# ShiftregisterTeil1.net
KiCad netlist of a schematic drawn in Altium Designer
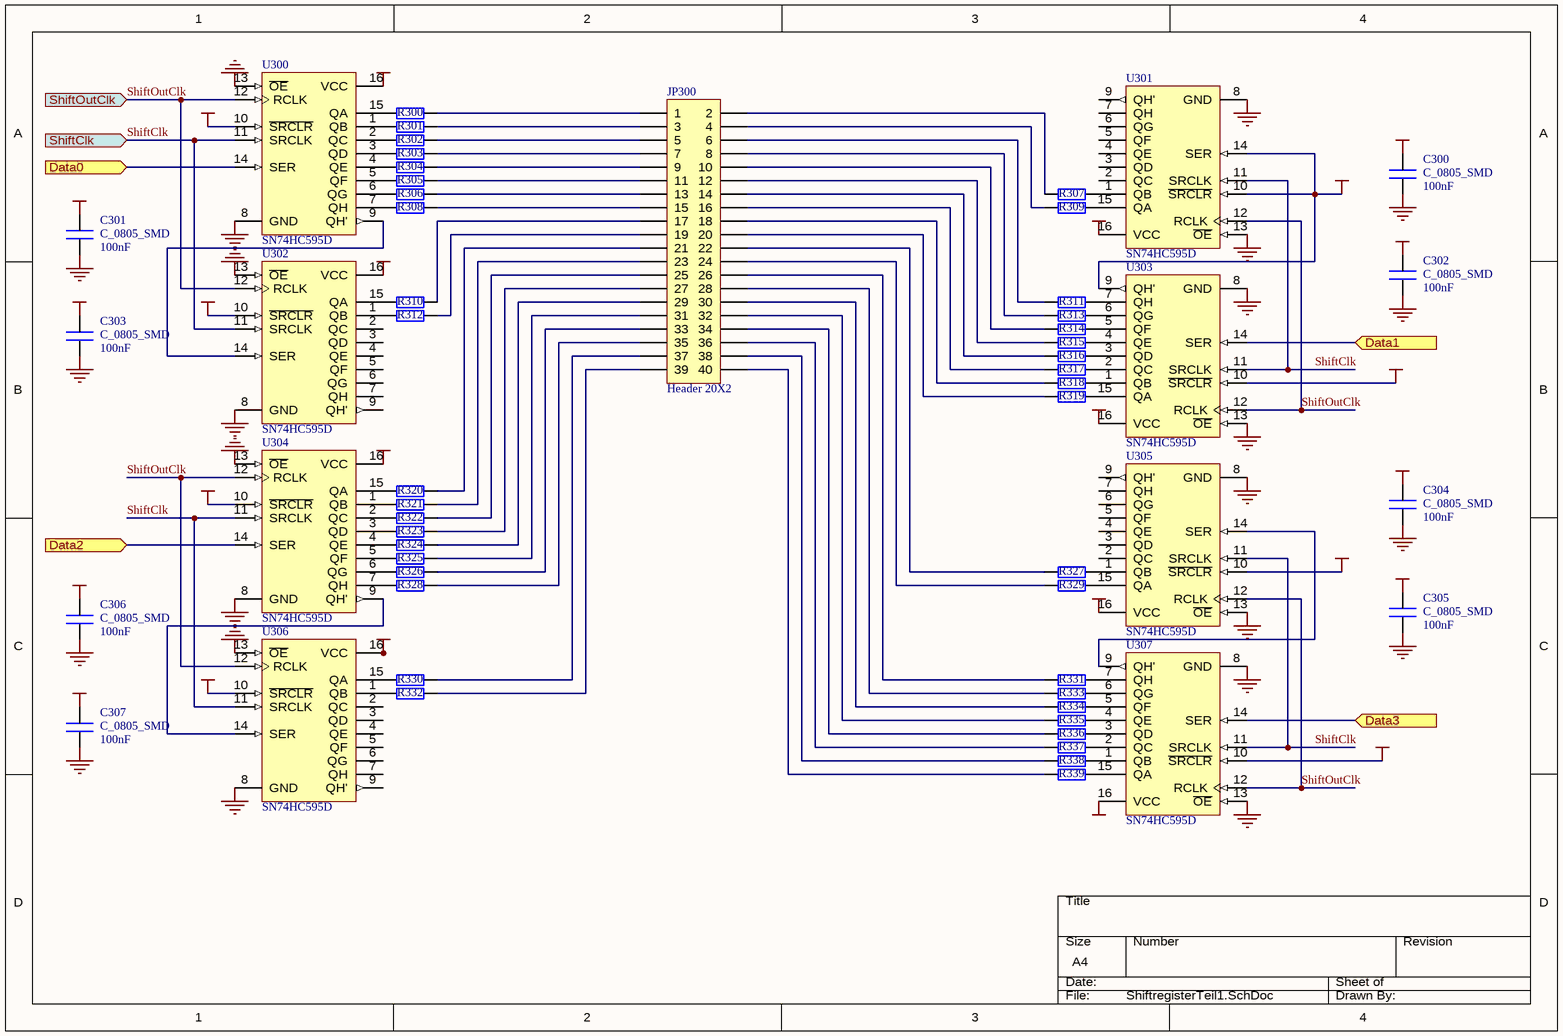
[diagram p0: ShiftregisterTeil1.SchDoc]

(export (version "E")
  (design (tool "Eeschema 10.0.6"))
  (components
    (comp (ref "C300")
      (value "C_0805_SMD")
      (footprint "0805_R")
      (description "Kondensator in SMD-Bauform")
      (fields (field (name "ALTIUM_UNNAMED_1") "100nF"))
      (libsource (lib "Kondensatoren") (part "C_0805_SMD"))
    )
    (comp (ref "C301")
      (value "C_0805_SMD")
      (footprint "0805_R")
      (description "Kondensator in SMD-Bauform")
      (fields (field (name "ALTIUM_UNNAMED_1") "100nF"))
      (libsource (lib "Kondensatoren") (part "C_0805_SMD"))
    )
    (comp (ref "C302")
      (value "C_0805_SMD")
      (footprint "0805_R")
      (description "Kondensator in SMD-Bauform")
      (fields (field (name "ALTIUM_UNNAMED_1") "100nF"))
      (libsource (lib "Kondensatoren") (part "C_0805_SMD"))
    )
    (comp (ref "C303")
      (value "C_0805_SMD")
      (footprint "0805_R")
      (description "Kondensator in SMD-Bauform")
      (fields (field (name "ALTIUM_UNNAMED_1") "100nF"))
      (libsource (lib "Kondensatoren") (part "C_0805_SMD"))
    )
    (comp (ref "C304")
      (value "C_0805_SMD")
      (footprint "0805_R")
      (description "Kondensator in SMD-Bauform")
      (fields (field (name "ALTIUM_UNNAMED_1") "100nF"))
      (libsource (lib "Kondensatoren") (part "C_0805_SMD"))
    )
    (comp (ref "C305")
      (value "C_0805_SMD")
      (footprint "0805_R")
      (description "Kondensator in SMD-Bauform")
      (fields (field (name "ALTIUM_UNNAMED_1") "100nF"))
      (libsource (lib "Kondensatoren") (part "C_0805_SMD"))
    )
    (comp (ref "C306")
      (value "C_0805_SMD")
      (footprint "0805_R")
      (description "Kondensator in SMD-Bauform")
      (fields (field (name "ALTIUM_UNNAMED_1") "100nF"))
      (libsource (lib "Kondensatoren") (part "C_0805_SMD"))
    )
    (comp (ref "C307")
      (value "C_0805_SMD")
      (footprint "0805_R")
      (description "Kondensator in SMD-Bauform")
      (fields (field (name "ALTIUM_UNNAMED_1") "100nF"))
      (libsource (lib "Kondensatoren") (part "C_0805_SMD"))
    )
    (comp (ref "JP300")
      (value "Header 20X2")
      (footprint "HDR2X20")
      (description "Header, 20-Pin, Dual row")
      (fields (field (name "PUBLISHER") "Altium Limited"))
      (libsource (lib "Miscellaneous Connectors") (part "Header 20X2"))
    )
    (comp (ref "R300")
      (value "PullUp")
      (footprint "CR2012-0805")
      (description "Resistor")
      (fields (field (name "PUBLISHER") "Altium Limited"))
      (libsource (lib "Miscellaneous Devices") (part "Res2"))
    )
    (comp (ref "R301")
      (value "PullUp")
      (footprint "CR2012-0805")
      (description "Resistor")
      (fields (field (name "PUBLISHER") "Altium Limited"))
      (libsource (lib "Miscellaneous Devices") (part "Res2"))
    )
    (comp (ref "R302")
      (value "PullUp")
      (footprint "CR2012-0805")
      (description "Resistor")
      (fields (field (name "PUBLISHER") "Altium Limited"))
      (libsource (lib "Miscellaneous Devices") (part "Res2"))
    )
    (comp (ref "R303")
      (value "PullUp")
      (footprint "CR2012-0805")
      (description "Resistor")
      (fields (field (name "PUBLISHER") "Altium Limited"))
      (libsource (lib "Miscellaneous Devices") (part "Res2"))
    )
    (comp (ref "R304")
      (value "PullUp")
      (footprint "CR2012-0805")
      (description "Resistor")
      (fields (field (name "PUBLISHER") "Altium Limited"))
      (libsource (lib "Miscellaneous Devices") (part "Res2"))
    )
    (comp (ref "R305")
      (value "PullUp")
      (footprint "CR2012-0805")
      (description "Resistor")
      (fields (field (name "PUBLISHER") "Altium Limited"))
      (libsource (lib "Miscellaneous Devices") (part "Res2"))
    )
    (comp (ref "R306")
      (value "PullUp")
      (footprint "CR2012-0805")
      (description "Resistor")
      (fields (field (name "PUBLISHER") "Altium Limited"))
      (libsource (lib "Miscellaneous Devices") (part "Res2"))
    )
    (comp (ref "R307")
      (value "PullUp")
      (footprint "CR2012-0805")
      (description "Resistor")
      (fields (field (name "PUBLISHER") "Altium Limited"))
      (libsource (lib "Miscellaneous Devices") (part "Res2"))
    )
    (comp (ref "R308")
      (value "PullUp")
      (footprint "CR2012-0805")
      (description "Resistor")
      (fields (field (name "PUBLISHER") "Altium Limited"))
      (libsource (lib "Miscellaneous Devices") (part "Res2"))
    )
    (comp (ref "R309")
      (value "PullUp")
      (footprint "CR2012-0805")
      (description "Resistor")
      (fields (field (name "PUBLISHER") "Altium Limited"))
      (libsource (lib "Miscellaneous Devices") (part "Res2"))
    )
    (comp (ref "R310")
      (value "PullUp")
      (footprint "CR2012-0805")
      (description "Resistor")
      (fields (field (name "PUBLISHER") "Altium Limited"))
      (libsource (lib "Miscellaneous Devices") (part "Res2"))
    )
    (comp (ref "R311")
      (value "PullUp")
      (footprint "CR2012-0805")
      (description "Resistor")
      (fields (field (name "PUBLISHER") "Altium Limited"))
      (libsource (lib "Miscellaneous Devices") (part "Res2"))
    )
    (comp (ref "R312")
      (value "PullUp")
      (footprint "CR2012-0805")
      (description "Resistor")
      (fields (field (name "PUBLISHER") "Altium Limited"))
      (libsource (lib "Miscellaneous Devices") (part "Res2"))
    )
    (comp (ref "R313")
      (value "PullUp")
      (footprint "CR2012-0805")
      (description "Resistor")
      (fields (field (name "PUBLISHER") "Altium Limited"))
      (libsource (lib "Miscellaneous Devices") (part "Res2"))
    )
    (comp (ref "R314")
      (value "PullUp")
      (footprint "CR2012-0805")
      (description "Resistor")
      (fields (field (name "PUBLISHER") "Altium Limited"))
      (libsource (lib "Miscellaneous Devices") (part "Res2"))
    )
    (comp (ref "R315")
      (value "PullUp")
      (footprint "CR2012-0805")
      (description "Resistor")
      (fields (field (name "PUBLISHER") "Altium Limited"))
      (libsource (lib "Miscellaneous Devices") (part "Res2"))
    )
    (comp (ref "R316")
      (value "PullUp")
      (footprint "CR2012-0805")
      (description "Resistor")
      (fields (field (name "PUBLISHER") "Altium Limited"))
      (libsource (lib "Miscellaneous Devices") (part "Res2"))
    )
    (comp (ref "R317")
      (value "PullUp")
      (footprint "CR2012-0805")
      (description "Resistor")
      (fields (field (name "PUBLISHER") "Altium Limited"))
      (libsource (lib "Miscellaneous Devices") (part "Res2"))
    )
    (comp (ref "R318")
      (value "PullUp")
      (footprint "CR2012-0805")
      (description "Resistor")
      (fields (field (name "PUBLISHER") "Altium Limited"))
      (libsource (lib "Miscellaneous Devices") (part "Res2"))
    )
    (comp (ref "R319")
      (value "PullUp")
      (footprint "CR2012-0805")
      (description "Resistor")
      (fields (field (name "PUBLISHER") "Altium Limited"))
      (libsource (lib "Miscellaneous Devices") (part "Res2"))
    )
    (comp (ref "R320")
      (value "PullUp")
      (footprint "CR2012-0805")
      (description "Resistor")
      (fields (field (name "PUBLISHER") "Altium Limited"))
      (libsource (lib "Miscellaneous Devices") (part "Res2"))
    )
    (comp (ref "R321")
      (value "PullUp")
      (footprint "CR2012-0805")
      (description "Resistor")
      (fields (field (name "PUBLISHER") "Altium Limited"))
      (libsource (lib "Miscellaneous Devices") (part "Res2"))
    )
    (comp (ref "R322")
      (value "PullUp")
      (footprint "CR2012-0805")
      (description "Resistor")
      (fields (field (name "PUBLISHER") "Altium Limited"))
      (libsource (lib "Miscellaneous Devices") (part "Res2"))
    )
    (comp (ref "R323")
      (value "PullUp")
      (footprint "CR2012-0805")
      (description "Resistor")
      (fields (field (name "PUBLISHER") "Altium Limited"))
      (libsource (lib "Miscellaneous Devices") (part "Res2"))
    )
    (comp (ref "R324")
      (value "PullUp")
      (footprint "CR2012-0805")
      (description "Resistor")
      (fields (field (name "PUBLISHER") "Altium Limited"))
      (libsource (lib "Miscellaneous Devices") (part "Res2"))
    )
    (comp (ref "R325")
      (value "PullUp")
      (footprint "CR2012-0805")
      (description "Resistor")
      (fields (field (name "PUBLISHER") "Altium Limited"))
      (libsource (lib "Miscellaneous Devices") (part "Res2"))
    )
    (comp (ref "R326")
      (value "PullUp")
      (footprint "CR2012-0805")
      (description "Resistor")
      (fields (field (name "PUBLISHER") "Altium Limited"))
      (libsource (lib "Miscellaneous Devices") (part "Res2"))
    )
    (comp (ref "R327")
      (value "PullUp")
      (footprint "CR2012-0805")
      (description "Resistor")
      (fields (field (name "PUBLISHER") "Altium Limited"))
      (libsource (lib "Miscellaneous Devices") (part "Res2"))
    )
    (comp (ref "R328")
      (value "PullUp")
      (footprint "CR2012-0805")
      (description "Resistor")
      (fields (field (name "PUBLISHER") "Altium Limited"))
      (libsource (lib "Miscellaneous Devices") (part "Res2"))
    )
    (comp (ref "R329")
      (value "PullUp")
      (footprint "CR2012-0805")
      (description "Resistor")
      (fields (field (name "PUBLISHER") "Altium Limited"))
      (libsource (lib "Miscellaneous Devices") (part "Res2"))
    )
    (comp (ref "R330")
      (value "PullUp")
      (footprint "CR2012-0805")
      (description "Resistor")
      (fields (field (name "PUBLISHER") "Altium Limited"))
      (libsource (lib "Miscellaneous Devices") (part "Res2"))
    )
    (comp (ref "R331")
      (value "PullUp")
      (footprint "CR2012-0805")
      (description "Resistor")
      (fields (field (name "PUBLISHER") "Altium Limited"))
      (libsource (lib "Miscellaneous Devices") (part "Res2"))
    )
    (comp (ref "R332")
      (value "PullUp")
      (footprint "CR2012-0805")
      (description "Resistor")
      (fields (field (name "PUBLISHER") "Altium Limited"))
      (libsource (lib "Miscellaneous Devices") (part "Res2"))
    )
    (comp (ref "R333")
      (value "PullUp")
      (footprint "CR2012-0805")
      (description "Resistor")
      (fields (field (name "PUBLISHER") "Altium Limited"))
      (libsource (lib "Miscellaneous Devices") (part "Res2"))
    )
    (comp (ref "R334")
      (value "PullUp")
      (footprint "CR2012-0805")
      (description "Resistor")
      (fields (field (name "PUBLISHER") "Altium Limited"))
      (libsource (lib "Miscellaneous Devices") (part "Res2"))
    )
    (comp (ref "R335")
      (value "PullUp")
      (footprint "CR2012-0805")
      (description "Resistor")
      (fields (field (name "PUBLISHER") "Altium Limited"))
      (libsource (lib "Miscellaneous Devices") (part "Res2"))
    )
    (comp (ref "R336")
      (value "PullUp")
      (footprint "CR2012-0805")
      (description "Resistor")
      (fields (field (name "PUBLISHER") "Altium Limited"))
      (libsource (lib "Miscellaneous Devices") (part "Res2"))
    )
    (comp (ref "R337")
      (value "PullUp")
      (footprint "CR2012-0805")
      (description "Resistor")
      (fields (field (name "PUBLISHER") "Altium Limited"))
      (libsource (lib "Miscellaneous Devices") (part "Res2"))
    )
    (comp (ref "R338")
      (value "PullUp")
      (footprint "CR2012-0805")
      (description "Resistor")
      (fields (field (name "PUBLISHER") "Altium Limited"))
      (libsource (lib "Miscellaneous Devices") (part "Res2"))
    )
    (comp (ref "R339")
      (value "PullUp")
      (footprint "CR2012-0805")
      (description "Resistor")
      (fields (field (name "PUBLISHER") "Altium Limited"))
      (libsource (lib "Miscellaneous Devices") (part "Res2"))
    )
    (comp (ref "U300")
      (value "SN74HC595D")
      (footprint "D016")
      (description "8-Bit Shift Register with 3-State Output Registers")
      (fields (field (name "PUBLISHER") "Altium Limited"))
      (libsource (lib "TI Logic Register") (part "SN74HC595D"))
    )
    (comp (ref "U301")
      (value "SN74HC595D")
      (footprint "D016")
      (description "8-Bit Shift Register with 3-State Output Registers")
      (fields (field (name "PUBLISHER") "Altium Limited"))
      (libsource (lib "") (part "SN74HC595D_1"))
    )
    (comp (ref "U302")
      (value "SN74HC595D")
      (footprint "D016")
      (description "8-Bit Shift Register with 3-State Output Registers")
      (fields (field (name "PUBLISHER") "Altium Limited"))
      (libsource (lib "TI Logic Register") (part "SN74HC595D"))
    )
    (comp (ref "U303")
      (value "SN74HC595D")
      (footprint "D016")
      (description "8-Bit Shift Register with 3-State Output Registers")
      (fields (field (name "PUBLISHER") "Altium Limited"))
      (libsource (lib "") (part "SN74HC595D_1"))
    )
    (comp (ref "U304")
      (value "SN74HC595D")
      (footprint "D016")
      (description "8-Bit Shift Register with 3-State Output Registers")
      (fields (field (name "PUBLISHER") "Altium Limited"))
      (libsource (lib "TI Logic Register") (part "SN74HC595D"))
    )
    (comp (ref "U305")
      (value "SN74HC595D")
      (footprint "D016")
      (description "8-Bit Shift Register with 3-State Output Registers")
      (fields (field (name "PUBLISHER") "Altium Limited"))
      (libsource (lib "") (part "SN74HC595D_1"))
    )
    (comp (ref "U306")
      (value "SN74HC595D")
      (footprint "D016")
      (description "8-Bit Shift Register with 3-State Output Registers")
      (fields (field (name "PUBLISHER") "Altium Limited"))
      (libsource (lib "TI Logic Register") (part "SN74HC595D"))
    )
    (comp (ref "U307")
      (value "SN74HC595D")
      (footprint "D016")
      (description "8-Bit Shift Register with 3-State Output Registers")
      (fields (field (name "PUBLISHER") "Altium Limited"))
      (libsource (lib "") (part "SN74HC595D_1"))
    )
  )
  (nets
    (net (code "1") (name "/Data0") (class "Default")
      (node (ref "U300") (pin "14") (pinfunction "SER_14") (pintype "input"))
    )
    (net (code "2") (name "/Data1") (class "Default")
      (node (ref "U303") (pin "14") (pinfunction "SER_14") (pintype "input"))
    )
    (net (code "3") (name "/Data2") (class "Default")
      (node (ref "U304") (pin "14") (pinfunction "SER_14") (pintype "input"))
    )
    (net (code "4") (name "/Data3") (class "Default")
      (node (ref "U307") (pin "14") (pinfunction "SER_14") (pintype "input"))
    )
    (net (code "5") (name "/ShiftClk") (class "Default")
      (node (ref "U300") (pin "11") (pinfunction "SRCLK_11") (pintype "input"))
      (node (ref "U301") (pin "11") (pinfunction "SRCLK_11") (pintype "input"))
      (node (ref "U302") (pin "11") (pinfunction "SRCLK_11") (pintype "input"))
      (node (ref "U303") (pin "11") (pinfunction "SRCLK_11") (pintype "input"))
      (node (ref "U304") (pin "11") (pinfunction "SRCLK_11") (pintype "input"))
      (node (ref "U305") (pin "11") (pinfunction "SRCLK_11") (pintype "input"))
      (node (ref "U306") (pin "11") (pinfunction "SRCLK_11") (pintype "input"))
      (node (ref "U307") (pin "11") (pinfunction "SRCLK_11") (pintype "input"))
    )
    (net (code "6") (name "/ShiftOutClk") (class "Default")
      (node (ref "U300") (pin "12") (pinfunction "RCLK_12") (pintype "input"))
      (node (ref "U301") (pin "12") (pinfunction "RCLK_12") (pintype "input"))
      (node (ref "U302") (pin "12") (pinfunction "RCLK_12") (pintype "input"))
      (node (ref "U303") (pin "12") (pinfunction "RCLK_12") (pintype "input"))
      (node (ref "U304") (pin "12") (pinfunction "RCLK_12") (pintype "input"))
      (node (ref "U305") (pin "12") (pinfunction "RCLK_12") (pintype "input"))
      (node (ref "U306") (pin "12") (pinfunction "RCLK_12") (pintype "input"))
      (node (ref "U307") (pin "12") (pinfunction "RCLK_12") (pintype "input"))
    )
    (net (code "7") (name "GND") (class "Default")
      (node (ref "C300") (pin "1") (pinfunction "1_1") (pintype "passive"))
      (node (ref "C301") (pin "1") (pinfunction "1_1") (pintype "passive"))
      (node (ref "C302") (pin "1") (pinfunction "1_1") (pintype "passive"))
      (node (ref "C303") (pin "1") (pinfunction "1_1") (pintype "passive"))
      (node (ref "C304") (pin "1") (pinfunction "1_1") (pintype "passive"))
      (node (ref "C305") (pin "1") (pinfunction "1_1") (pintype "passive"))
      (node (ref "C306") (pin "1") (pinfunction "1_1") (pintype "passive"))
      (node (ref "C307") (pin "1") (pinfunction "1_1") (pintype "passive"))
      (node (ref "U300") (pin "13") (pinfunction "~{OE}_13") (pintype "input"))
      (node (ref "U300") (pin "8") (pinfunction "GND_8") (pintype "power_in"))
      (node (ref "U301") (pin "13") (pinfunction "~{OE}_13") (pintype "input"))
      (node (ref "U301") (pin "8") (pinfunction "GND_8") (pintype "power_in"))
      (node (ref "U302") (pin "13") (pinfunction "~{OE}_13") (pintype "input"))
      (node (ref "U302") (pin "8") (pinfunction "GND_8") (pintype "power_in"))
      (node (ref "U303") (pin "13") (pinfunction "~{OE}_13") (pintype "input"))
      (node (ref "U303") (pin "8") (pinfunction "GND_8") (pintype "power_in"))
      (node (ref "U304") (pin "13") (pinfunction "~{OE}_13") (pintype "input"))
      (node (ref "U304") (pin "8") (pinfunction "GND_8") (pintype "power_in"))
      (node (ref "U305") (pin "13") (pinfunction "~{OE}_13") (pintype "input"))
      (node (ref "U305") (pin "8") (pinfunction "GND_8") (pintype "power_in"))
      (node (ref "U306") (pin "13") (pinfunction "~{OE}_13") (pintype "input"))
      (node (ref "U306") (pin "8") (pinfunction "GND_8") (pintype "power_in"))
      (node (ref "U307") (pin "13") (pinfunction "~{OE}_13") (pintype "input"))
      (node (ref "U307") (pin "8") (pinfunction "GND_8") (pintype "power_in"))
    )
    (net (code "8") (name "Net-(JP300-Pad1)") (class "Default")
      (node (ref "JP300") (pin "1") (pinfunction "1_1") (pintype "passive"))
      (node (ref "R300") (pin "1") (pinfunction "1_1") (pintype "passive"))
    )
    (net (code "9") (name "Net-(JP300-Pad2)") (class "Default")
      (node (ref "JP300") (pin "2") (pinfunction "2_2") (pintype "passive"))
      (node (ref "R307") (pin "2") (pinfunction "2_2") (pintype "passive"))
    )
    (net (code "10") (name "Net-(JP300-Pad3)") (class "Default")
      (node (ref "JP300") (pin "3") (pinfunction "3_3") (pintype "passive"))
      (node (ref "R301") (pin "1") (pinfunction "1_1") (pintype "passive"))
    )
    (net (code "11") (name "Net-(JP300-Pad4)") (class "Default")
      (node (ref "JP300") (pin "4") (pinfunction "4_4") (pintype "passive"))
      (node (ref "R309") (pin "2") (pinfunction "2_2") (pintype "passive"))
    )
    (net (code "12") (name "Net-(JP300-Pad5)") (class "Default")
      (node (ref "JP300") (pin "5") (pinfunction "5_5") (pintype "passive"))
      (node (ref "R302") (pin "1") (pinfunction "1_1") (pintype "passive"))
    )
    (net (code "13") (name "Net-(JP300-Pad6)") (class "Default")
      (node (ref "JP300") (pin "6") (pinfunction "6_6") (pintype "passive"))
      (node (ref "R311") (pin "2") (pinfunction "2_2") (pintype "passive"))
    )
    (net (code "14") (name "Net-(JP300-Pad7)") (class "Default")
      (node (ref "JP300") (pin "7") (pinfunction "7_7") (pintype "passive"))
      (node (ref "R303") (pin "1") (pinfunction "1_1") (pintype "passive"))
    )
    (net (code "15") (name "Net-(JP300-Pad8)") (class "Default")
      (node (ref "JP300") (pin "8") (pinfunction "8_8") (pintype "passive"))
      (node (ref "R313") (pin "2") (pinfunction "2_2") (pintype "passive"))
    )
    (net (code "16") (name "Net-(JP300-Pad9)") (class "Default")
      (node (ref "JP300") (pin "9") (pinfunction "9_9") (pintype "passive"))
      (node (ref "R304") (pin "1") (pinfunction "1_1") (pintype "passive"))
    )
    (net (code "17") (name "Net-(JP300-Pad10)") (class "Default")
      (node (ref "JP300") (pin "10") (pinfunction "10_10") (pintype "passive"))
      (node (ref "R314") (pin "2") (pinfunction "2_2") (pintype "passive"))
    )
    (net (code "18") (name "Net-(JP300-Pad11)") (class "Default")
      (node (ref "JP300") (pin "11") (pinfunction "11_11") (pintype "passive"))
      (node (ref "R305") (pin "1") (pinfunction "1_1") (pintype "passive"))
    )
    (net (code "19") (name "Net-(JP300-Pad12)") (class "Default")
      (node (ref "JP300") (pin "12") (pinfunction "12_12") (pintype "passive"))
      (node (ref "R315") (pin "2") (pinfunction "2_2") (pintype "passive"))
    )
    (net (code "20") (name "Net-(JP300-Pad13)") (class "Default")
      (node (ref "JP300") (pin "13") (pinfunction "13_13") (pintype "passive"))
      (node (ref "R306") (pin "1") (pinfunction "1_1") (pintype "passive"))
    )
    (net (code "21") (name "Net-(JP300-Pad14)") (class "Default")
      (node (ref "JP300") (pin "14") (pinfunction "14_14") (pintype "passive"))
      (node (ref "R316") (pin "2") (pinfunction "2_2") (pintype "passive"))
    )
    (net (code "22") (name "Net-(JP300-Pad15)") (class "Default")
      (node (ref "JP300") (pin "15") (pinfunction "15_15") (pintype "passive"))
      (node (ref "R308") (pin "1") (pinfunction "1_1") (pintype "passive"))
    )
    (net (code "23") (name "Net-(JP300-Pad16)") (class "Default")
      (node (ref "JP300") (pin "16") (pinfunction "16_16") (pintype "passive"))
      (node (ref "R317") (pin "2") (pinfunction "2_2") (pintype "passive"))
    )
    (net (code "24") (name "Net-(JP300-Pad17)") (class "Default")
      (node (ref "JP300") (pin "17") (pinfunction "17_17") (pintype "passive"))
      (node (ref "R310") (pin "1") (pinfunction "1_1") (pintype "passive"))
    )
    (net (code "25") (name "Net-(JP300-Pad18)") (class "Default")
      (node (ref "JP300") (pin "18") (pinfunction "18_18") (pintype "passive"))
      (node (ref "R318") (pin "2") (pinfunction "2_2") (pintype "passive"))
    )
    (net (code "26") (name "Net-(JP300-Pad19)") (class "Default")
      (node (ref "JP300") (pin "19") (pinfunction "19_19") (pintype "passive"))
      (node (ref "R312") (pin "1") (pinfunction "1_1") (pintype "passive"))
    )
    (net (code "27") (name "Net-(JP300-Pad20)") (class "Default")
      (node (ref "JP300") (pin "20") (pinfunction "20_20") (pintype "passive"))
      (node (ref "R319") (pin "2") (pinfunction "2_2") (pintype "passive"))
    )
    (net (code "28") (name "Net-(JP300-Pad21)") (class "Default")
      (node (ref "JP300") (pin "21") (pinfunction "21_21") (pintype "passive"))
      (node (ref "R320") (pin "1") (pinfunction "1_1") (pintype "passive"))
    )
    (net (code "29") (name "Net-(JP300-Pad22)") (class "Default")
      (node (ref "JP300") (pin "22") (pinfunction "22_22") (pintype "passive"))
      (node (ref "R327") (pin "2") (pinfunction "2_2") (pintype "passive"))
    )
    (net (code "30") (name "Net-(JP300-Pad23)") (class "Default")
      (node (ref "JP300") (pin "23") (pinfunction "23_23") (pintype "passive"))
      (node (ref "R321") (pin "1") (pinfunction "1_1") (pintype "passive"))
    )
    (net (code "31") (name "Net-(JP300-Pad24)") (class "Default")
      (node (ref "JP300") (pin "24") (pinfunction "24_24") (pintype "passive"))
      (node (ref "R329") (pin "2") (pinfunction "2_2") (pintype "passive"))
    )
    (net (code "32") (name "Net-(JP300-Pad25)") (class "Default")
      (node (ref "JP300") (pin "25") (pinfunction "25_25") (pintype "passive"))
      (node (ref "R322") (pin "1") (pinfunction "1_1") (pintype "passive"))
    )
    (net (code "33") (name "Net-(JP300-Pad26)") (class "Default")
      (node (ref "JP300") (pin "26") (pinfunction "26_26") (pintype "passive"))
      (node (ref "R331") (pin "2") (pinfunction "2_2") (pintype "passive"))
    )
    (net (code "34") (name "Net-(JP300-Pad27)") (class "Default")
      (node (ref "JP300") (pin "27") (pinfunction "27_27") (pintype "passive"))
      (node (ref "R323") (pin "1") (pinfunction "1_1") (pintype "passive"))
    )
    (net (code "35") (name "Net-(JP300-Pad28)") (class "Default")
      (node (ref "JP300") (pin "28") (pinfunction "28_28") (pintype "passive"))
      (node (ref "R333") (pin "2") (pinfunction "2_2") (pintype "passive"))
    )
    (net (code "36") (name "Net-(JP300-Pad29)") (class "Default")
      (node (ref "JP300") (pin "29") (pinfunction "29_29") (pintype "passive"))
      (node (ref "R324") (pin "1") (pinfunction "1_1") (pintype "passive"))
    )
    (net (code "37") (name "Net-(JP300-Pad30)") (class "Default")
      (node (ref "JP300") (pin "30") (pinfunction "30_30") (pintype "passive"))
      (node (ref "R334") (pin "2") (pinfunction "2_2") (pintype "passive"))
    )
    (net (code "38") (name "Net-(JP300-Pad31)") (class "Default")
      (node (ref "JP300") (pin "31") (pinfunction "31_31") (pintype "passive"))
      (node (ref "R325") (pin "1") (pinfunction "1_1") (pintype "passive"))
    )
    (net (code "39") (name "Net-(JP300-Pad32)") (class "Default")
      (node (ref "JP300") (pin "32") (pinfunction "32_32") (pintype "passive"))
      (node (ref "R335") (pin "2") (pinfunction "2_2") (pintype "passive"))
    )
    (net (code "40") (name "Net-(JP300-Pad33)") (class "Default")
      (node (ref "JP300") (pin "33") (pinfunction "33_33") (pintype "passive"))
      (node (ref "R326") (pin "1") (pinfunction "1_1") (pintype "passive"))
    )
    (net (code "41") (name "Net-(JP300-Pad34)") (class "Default")
      (node (ref "JP300") (pin "34") (pinfunction "34_34") (pintype "passive"))
      (node (ref "R336") (pin "2") (pinfunction "2_2") (pintype "passive"))
    )
    (net (code "42") (name "Net-(JP300-Pad35)") (class "Default")
      (node (ref "JP300") (pin "35") (pinfunction "35_35") (pintype "passive"))
      (node (ref "R328") (pin "1") (pinfunction "1_1") (pintype "passive"))
    )
    (net (code "43") (name "Net-(JP300-Pad36)") (class "Default")
      (node (ref "JP300") (pin "36") (pinfunction "36_36") (pintype "passive"))
      (node (ref "R337") (pin "2") (pinfunction "2_2") (pintype "passive"))
    )
    (net (code "44") (name "Net-(JP300-Pad37)") (class "Default")
      (node (ref "JP300") (pin "37") (pinfunction "37_37") (pintype "passive"))
      (node (ref "R330") (pin "1") (pinfunction "1_1") (pintype "passive"))
    )
    (net (code "45") (name "Net-(JP300-Pad38)") (class "Default")
      (node (ref "JP300") (pin "38") (pinfunction "38_38") (pintype "passive"))
      (node (ref "R338") (pin "2") (pinfunction "2_2") (pintype "passive"))
    )
    (net (code "46") (name "Net-(JP300-Pad39)") (class "Default")
      (node (ref "JP300") (pin "39") (pinfunction "39_39") (pintype "passive"))
      (node (ref "R332") (pin "1") (pinfunction "1_1") (pintype "passive"))
    )
    (net (code "47") (name "Net-(JP300-Pad40)") (class "Default")
      (node (ref "JP300") (pin "40") (pinfunction "40_40") (pintype "passive"))
      (node (ref "R339") (pin "2") (pinfunction "2_2") (pintype "passive"))
    )
    (net (code "48") (name "Net-(U300-QA)") (class "Default")
      (node (ref "R300") (pin "2") (pinfunction "2_2") (pintype "passive"))
      (node (ref "U300") (pin "15") (pinfunction "QA_15") (pintype "tri_state"))
    )
    (net (code "49") (name "Net-(U300-QB)") (class "Default")
      (node (ref "R301") (pin "2") (pinfunction "2_2") (pintype "passive"))
      (node (ref "U300") (pin "1") (pinfunction "QB_1") (pintype "tri_state"))
    )
    (net (code "50") (name "Net-(U300-QC)") (class "Default")
      (node (ref "R302") (pin "2") (pinfunction "2_2") (pintype "passive"))
      (node (ref "U300") (pin "2") (pinfunction "QC_2") (pintype "tri_state"))
    )
    (net (code "51") (name "Net-(U300-QD)") (class "Default")
      (node (ref "R303") (pin "2") (pinfunction "2_2") (pintype "passive"))
      (node (ref "U300") (pin "3") (pinfunction "QD_3") (pintype "tri_state"))
    )
    (net (code "52") (name "Net-(U300-QE)") (class "Default")
      (node (ref "R304") (pin "2") (pinfunction "2_2") (pintype "passive"))
      (node (ref "U300") (pin "4") (pinfunction "QE_4") (pintype "tri_state"))
    )
    (net (code "53") (name "Net-(U300-QF)") (class "Default")
      (node (ref "R305") (pin "2") (pinfunction "2_2") (pintype "passive"))
      (node (ref "U300") (pin "5") (pinfunction "QF_5") (pintype "tri_state"))
    )
    (net (code "54") (name "Net-(U300-QG)") (class "Default")
      (node (ref "R306") (pin "2") (pinfunction "2_2") (pintype "passive"))
      (node (ref "U300") (pin "6") (pinfunction "QG_6") (pintype "tri_state"))
    )
    (net (code "55") (name "Net-(U300-QH')") (class "Default")
      (node (ref "U300") (pin "9") (pinfunction "QH'_9") (pintype "output"))
      (node (ref "U302") (pin "14") (pinfunction "SER_14") (pintype "input"))
    )
    (net (code "56") (name "Net-(U300-QH)") (class "Default")
      (node (ref "R308") (pin "2") (pinfunction "2_2") (pintype "passive"))
      (node (ref "U300") (pin "7") (pinfunction "QH_7") (pintype "tri_state"))
    )
    (net (code "57") (name "Net-(U301-QA)") (class "Default")
      (node (ref "R309") (pin "1") (pinfunction "1_1") (pintype "passive"))
      (node (ref "U301") (pin "15") (pinfunction "QA_15") (pintype "tri_state"))
    )
    (net (code "58") (name "Net-(U301-QB)") (class "Default")
      (node (ref "R307") (pin "1") (pinfunction "1_1") (pintype "passive"))
      (node (ref "U301") (pin "1") (pinfunction "QB_1") (pintype "tri_state"))
    )
    (net (code "59") (name "Net-(U302-QA)") (class "Default")
      (node (ref "R310") (pin "2") (pinfunction "2_2") (pintype "passive"))
      (node (ref "U302") (pin "15") (pinfunction "QA_15") (pintype "tri_state"))
    )
    (net (code "60") (name "Net-(U302-QB)") (class "Default")
      (node (ref "R312") (pin "2") (pinfunction "2_2") (pintype "passive"))
      (node (ref "U302") (pin "1") (pinfunction "QB_1") (pintype "tri_state"))
    )
    (net (code "61") (name "Net-(U303-QA)") (class "Default")
      (node (ref "R319") (pin "1") (pinfunction "1_1") (pintype "passive"))
      (node (ref "U303") (pin "15") (pinfunction "QA_15") (pintype "tri_state"))
    )
    (net (code "62") (name "Net-(U303-QB)") (class "Default")
      (node (ref "R318") (pin "1") (pinfunction "1_1") (pintype "passive"))
      (node (ref "U303") (pin "1") (pinfunction "QB_1") (pintype "tri_state"))
    )
    (net (code "63") (name "Net-(U303-QC)") (class "Default")
      (node (ref "R317") (pin "1") (pinfunction "1_1") (pintype "passive"))
      (node (ref "U303") (pin "2") (pinfunction "QC_2") (pintype "tri_state"))
    )
    (net (code "64") (name "Net-(U303-QD)") (class "Default")
      (node (ref "R316") (pin "1") (pinfunction "1_1") (pintype "passive"))
      (node (ref "U303") (pin "3") (pinfunction "QD_3") (pintype "tri_state"))
    )
    (net (code "65") (name "Net-(U303-QE)") (class "Default")
      (node (ref "R315") (pin "1") (pinfunction "1_1") (pintype "passive"))
      (node (ref "U303") (pin "4") (pinfunction "QE_4") (pintype "tri_state"))
    )
    (net (code "66") (name "Net-(U303-QF)") (class "Default")
      (node (ref "R314") (pin "1") (pinfunction "1_1") (pintype "passive"))
      (node (ref "U303") (pin "5") (pinfunction "QF_5") (pintype "tri_state"))
    )
    (net (code "67") (name "Net-(U303-QG)") (class "Default")
      (node (ref "R313") (pin "1") (pinfunction "1_1") (pintype "passive"))
      (node (ref "U303") (pin "6") (pinfunction "QG_6") (pintype "tri_state"))
    )
    (net (code "68") (name "Net-(U303-QH)") (class "Default")
      (node (ref "R311") (pin "1") (pinfunction "1_1") (pintype "passive"))
      (node (ref "U303") (pin "7") (pinfunction "QH_7") (pintype "tri_state"))
    )
    (net (code "69") (name "Net-(U304-QA)") (class "Default")
      (node (ref "R320") (pin "2") (pinfunction "2_2") (pintype "passive"))
      (node (ref "U304") (pin "15") (pinfunction "QA_15") (pintype "tri_state"))
    )
    (net (code "70") (name "Net-(U304-QB)") (class "Default")
      (node (ref "R321") (pin "2") (pinfunction "2_2") (pintype "passive"))
      (node (ref "U304") (pin "1") (pinfunction "QB_1") (pintype "tri_state"))
    )
    (net (code "71") (name "Net-(U304-QC)") (class "Default")
      (node (ref "R322") (pin "2") (pinfunction "2_2") (pintype "passive"))
      (node (ref "U304") (pin "2") (pinfunction "QC_2") (pintype "tri_state"))
    )
    (net (code "72") (name "Net-(U304-QD)") (class "Default")
      (node (ref "R323") (pin "2") (pinfunction "2_2") (pintype "passive"))
      (node (ref "U304") (pin "3") (pinfunction "QD_3") (pintype "tri_state"))
    )
    (net (code "73") (name "Net-(U304-QE)") (class "Default")
      (node (ref "R324") (pin "2") (pinfunction "2_2") (pintype "passive"))
      (node (ref "U304") (pin "4") (pinfunction "QE_4") (pintype "tri_state"))
    )
    (net (code "74") (name "Net-(U304-QF)") (class "Default")
      (node (ref "R325") (pin "2") (pinfunction "2_2") (pintype "passive"))
      (node (ref "U304") (pin "5") (pinfunction "QF_5") (pintype "tri_state"))
    )
    (net (code "75") (name "Net-(U304-QG)") (class "Default")
      (node (ref "R326") (pin "2") (pinfunction "2_2") (pintype "passive"))
      (node (ref "U304") (pin "6") (pinfunction "QG_6") (pintype "tri_state"))
    )
    (net (code "76") (name "Net-(U304-QH')") (class "Default")
      (node (ref "U304") (pin "9") (pinfunction "QH'_9") (pintype "output"))
      (node (ref "U306") (pin "14") (pinfunction "SER_14") (pintype "input"))
    )
    (net (code "77") (name "Net-(U304-QH)") (class "Default")
      (node (ref "R328") (pin "2") (pinfunction "2_2") (pintype "passive"))
      (node (ref "U304") (pin "7") (pinfunction "QH_7") (pintype "tri_state"))
    )
    (net (code "78") (name "Net-(U305-QA)") (class "Default")
      (node (ref "R329") (pin "1") (pinfunction "1_1") (pintype "passive"))
      (node (ref "U305") (pin "15") (pinfunction "QA_15") (pintype "tri_state"))
    )
    (net (code "79") (name "Net-(U305-QB)") (class "Default")
      (node (ref "R327") (pin "1") (pinfunction "1_1") (pintype "passive"))
      (node (ref "U305") (pin "1") (pinfunction "QB_1") (pintype "tri_state"))
    )
    (net (code "80") (name "Net-(U305-SER)") (class "Default")
      (node (ref "U305") (pin "14") (pinfunction "SER_14") (pintype "input"))
      (node (ref "U307") (pin "9") (pinfunction "QH'_9") (pintype "output"))
    )
    (net (code "81") (name "Net-(U306-QA)") (class "Default")
      (node (ref "R330") (pin "2") (pinfunction "2_2") (pintype "passive"))
      (node (ref "U306") (pin "15") (pinfunction "QA_15") (pintype "tri_state"))
    )
    (net (code "82") (name "Net-(U306-QB)") (class "Default")
      (node (ref "R332") (pin "2") (pinfunction "2_2") (pintype "passive"))
      (node (ref "U306") (pin "1") (pinfunction "QB_1") (pintype "tri_state"))
    )
    (net (code "83") (name "Net-(U307-QA)") (class "Default")
      (node (ref "R339") (pin "1") (pinfunction "1_1") (pintype "passive"))
      (node (ref "U307") (pin "15") (pinfunction "QA_15") (pintype "tri_state"))
    )
    (net (code "84") (name "Net-(U307-QB)") (class "Default")
      (node (ref "R338") (pin "1") (pinfunction "1_1") (pintype "passive"))
      (node (ref "U307") (pin "1") (pinfunction "QB_1") (pintype "tri_state"))
    )
    (net (code "85") (name "Net-(U307-QC)") (class "Default")
      (node (ref "R337") (pin "1") (pinfunction "1_1") (pintype "passive"))
      (node (ref "U307") (pin "2") (pinfunction "QC_2") (pintype "tri_state"))
    )
    (net (code "86") (name "Net-(U307-QD)") (class "Default")
      (node (ref "R336") (pin "1") (pinfunction "1_1") (pintype "passive"))
      (node (ref "U307") (pin "3") (pinfunction "QD_3") (pintype "tri_state"))
    )
    (net (code "87") (name "Net-(U307-QE)") (class "Default")
      (node (ref "R335") (pin "1") (pinfunction "1_1") (pintype "passive"))
      (node (ref "U307") (pin "4") (pinfunction "QE_4") (pintype "tri_state"))
    )
    (net (code "88") (name "Net-(U307-QF)") (class "Default")
      (node (ref "R334") (pin "1") (pinfunction "1_1") (pintype "passive"))
      (node (ref "U307") (pin "5") (pinfunction "QF_5") (pintype "tri_state"))
    )
    (net (code "89") (name "Net-(U307-QG)") (class "Default")
      (node (ref "R333") (pin "1") (pinfunction "1_1") (pintype "passive"))
      (node (ref "U307") (pin "6") (pinfunction "QG_6") (pintype "tri_state"))
    )
    (net (code "90") (name "Net-(U307-QH)") (class "Default")
      (node (ref "R331") (pin "1") (pinfunction "1_1") (pintype "passive"))
      (node (ref "U307") (pin "7") (pinfunction "QH_7") (pintype "tri_state"))
    )
    (net (code "91") (name "VCC") (class "Default")
      (node (ref "C300") (pin "2") (pinfunction "2_2") (pintype "passive"))
      (node (ref "C301") (pin "2") (pinfunction "2_2") (pintype "passive"))
      (node (ref "C302") (pin "2") (pinfunction "2_2") (pintype "passive"))
      (node (ref "C303") (pin "2") (pinfunction "2_2") (pintype "passive"))
      (node (ref "C304") (pin "2") (pinfunction "2_2") (pintype "passive"))
      (node (ref "C305") (pin "2") (pinfunction "2_2") (pintype "passive"))
      (node (ref "C306") (pin "2") (pinfunction "2_2") (pintype "passive"))
      (node (ref "C307") (pin "2") (pinfunction "2_2") (pintype "passive"))
      (node (ref "U300") (pin "10") (pinfunction "~{SRCLR}_10") (pintype "input"))
      (node (ref "U300") (pin "16") (pinfunction "VCC_16") (pintype "power_in"))
      (node (ref "U301") (pin "10") (pinfunction "~{SRCLR}_10") (pintype "input"))
      (node (ref "U301") (pin "14") (pinfunction "SER_14") (pintype "input"))
      (node (ref "U301") (pin "16") (pinfunction "VCC_16") (pintype "power_in"))
      (node (ref "U302") (pin "10") (pinfunction "~{SRCLR}_10") (pintype "input"))
      (node (ref "U302") (pin "16") (pinfunction "VCC_16") (pintype "power_in"))
      (node (ref "U303") (pin "10") (pinfunction "~{SRCLR}_10") (pintype "input"))
      (node (ref "U303") (pin "16") (pinfunction "VCC_16") (pintype "power_in"))
      (node (ref "U303") (pin "9") (pinfunction "QH'_9") (pintype "output"))
      (node (ref "U304") (pin "10") (pinfunction "~{SRCLR}_10") (pintype "input"))
      (node (ref "U304") (pin "16") (pinfunction "VCC_16") (pintype "power_in"))
      (node (ref "U305") (pin "10") (pinfunction "~{SRCLR}_10") (pintype "input"))
      (node (ref "U305") (pin "16") (pinfunction "VCC_16") (pintype "power_in"))
      (node (ref "U306") (pin "10") (pinfunction "~{SRCLR}_10") (pintype "input"))
      (node (ref "U306") (pin "16") (pinfunction "VCC_16") (pintype "power_in"))
      (node (ref "U307") (pin "10") (pinfunction "~{SRCLR}_10") (pintype "input"))
      (node (ref "U307") (pin "16") (pinfunction "VCC_16") (pintype "power_in"))
    )
    (net (code "92") (name "unconnected-(U301-QC-Pad2)") (class "Default")
      (node (ref "U301") (pin "2") (pinfunction "QC_2") (pintype "tri_state"))
    )
    (net (code "93") (name "unconnected-(U301-QD-Pad3)") (class "Default")
      (node (ref "U301") (pin "3") (pinfunction "QD_3") (pintype "tri_state"))
    )
    (net (code "94") (name "unconnected-(U301-QE-Pad4)") (class "Default")
      (node (ref "U301") (pin "4") (pinfunction "QE_4") (pintype "tri_state"))
    )
    (net (code "95") (name "unconnected-(U301-QF-Pad5)") (class "Default")
      (node (ref "U301") (pin "5") (pinfunction "QF_5") (pintype "tri_state"))
    )
    (net (code "96") (name "unconnected-(U301-QG-Pad6)") (class "Default")
      (node (ref "U301") (pin "6") (pinfunction "QG_6") (pintype "tri_state"))
    )
    (net (code "97") (name "unconnected-(U301-QH'-Pad9)") (class "Default")
      (node (ref "U301") (pin "9") (pinfunction "QH'_9") (pintype "output"))
    )
    (net (code "98") (name "unconnected-(U301-QH-Pad7)") (class "Default")
      (node (ref "U301") (pin "7") (pinfunction "QH_7") (pintype "tri_state"))
    )
    (net (code "99") (name "unconnected-(U302-QC-Pad2)") (class "Default")
      (node (ref "U302") (pin "2") (pinfunction "QC_2") (pintype "tri_state"))
    )
    (net (code "100") (name "unconnected-(U302-QD-Pad3)") (class "Default")
      (node (ref "U302") (pin "3") (pinfunction "QD_3") (pintype "tri_state"))
    )
    (net (code "101") (name "unconnected-(U302-QE-Pad4)") (class "Default")
      (node (ref "U302") (pin "4") (pinfunction "QE_4") (pintype "tri_state"))
    )
    (net (code "102") (name "unconnected-(U302-QF-Pad5)") (class "Default")
      (node (ref "U302") (pin "5") (pinfunction "QF_5") (pintype "tri_state"))
    )
    (net (code "103") (name "unconnected-(U302-QG-Pad6)") (class "Default")
      (node (ref "U302") (pin "6") (pinfunction "QG_6") (pintype "tri_state"))
    )
    (net (code "104") (name "unconnected-(U302-QH'-Pad9)") (class "Default")
      (node (ref "U302") (pin "9") (pinfunction "QH'_9") (pintype "output"))
    )
    (net (code "105") (name "unconnected-(U302-QH-Pad7)") (class "Default")
      (node (ref "U302") (pin "7") (pinfunction "QH_7") (pintype "tri_state"))
    )
    (net (code "106") (name "unconnected-(U305-QC-Pad2)") (class "Default")
      (node (ref "U305") (pin "2") (pinfunction "QC_2") (pintype "tri_state"))
    )
    (net (code "107") (name "unconnected-(U305-QD-Pad3)") (class "Default")
      (node (ref "U305") (pin "3") (pinfunction "QD_3") (pintype "tri_state"))
    )
    (net (code "108") (name "unconnected-(U305-QE-Pad4)") (class "Default")
      (node (ref "U305") (pin "4") (pinfunction "QE_4") (pintype "tri_state"))
    )
    (net (code "109") (name "unconnected-(U305-QF-Pad5)") (class "Default")
      (node (ref "U305") (pin "5") (pinfunction "QF_5") (pintype "tri_state"))
    )
    (net (code "110") (name "unconnected-(U305-QG-Pad6)") (class "Default")
      (node (ref "U305") (pin "6") (pinfunction "QG_6") (pintype "tri_state"))
    )
    (net (code "111") (name "unconnected-(U305-QH'-Pad9)") (class "Default")
      (node (ref "U305") (pin "9") (pinfunction "QH'_9") (pintype "output"))
    )
    (net (code "112") (name "unconnected-(U305-QH-Pad7)") (class "Default")
      (node (ref "U305") (pin "7") (pinfunction "QH_7") (pintype "tri_state"))
    )
    (net (code "113") (name "unconnected-(U306-QC-Pad2)") (class "Default")
      (node (ref "U306") (pin "2") (pinfunction "QC_2") (pintype "tri_state"))
    )
    (net (code "114") (name "unconnected-(U306-QD-Pad3)") (class "Default")
      (node (ref "U306") (pin "3") (pinfunction "QD_3") (pintype "tri_state"))
    )
    (net (code "115") (name "unconnected-(U306-QE-Pad4)") (class "Default")
      (node (ref "U306") (pin "4") (pinfunction "QE_4") (pintype "tri_state"))
    )
    (net (code "116") (name "unconnected-(U306-QF-Pad5)") (class "Default")
      (node (ref "U306") (pin "5") (pinfunction "QF_5") (pintype "tri_state"))
    )
    (net (code "117") (name "unconnected-(U306-QG-Pad6)") (class "Default")
      (node (ref "U306") (pin "6") (pinfunction "QG_6") (pintype "tri_state"))
    )
    (net (code "118") (name "unconnected-(U306-QH'-Pad9)") (class "Default")
      (node (ref "U306") (pin "9") (pinfunction "QH'_9") (pintype "output"))
    )
    (net (code "119") (name "unconnected-(U306-QH-Pad7)") (class "Default")
      (node (ref "U306") (pin "7") (pinfunction "QH_7") (pintype "tri_state"))
    )
  )
)
